# 06_RPI_USB.net
KiCad netlist of a schematic drawn in Altium Designer
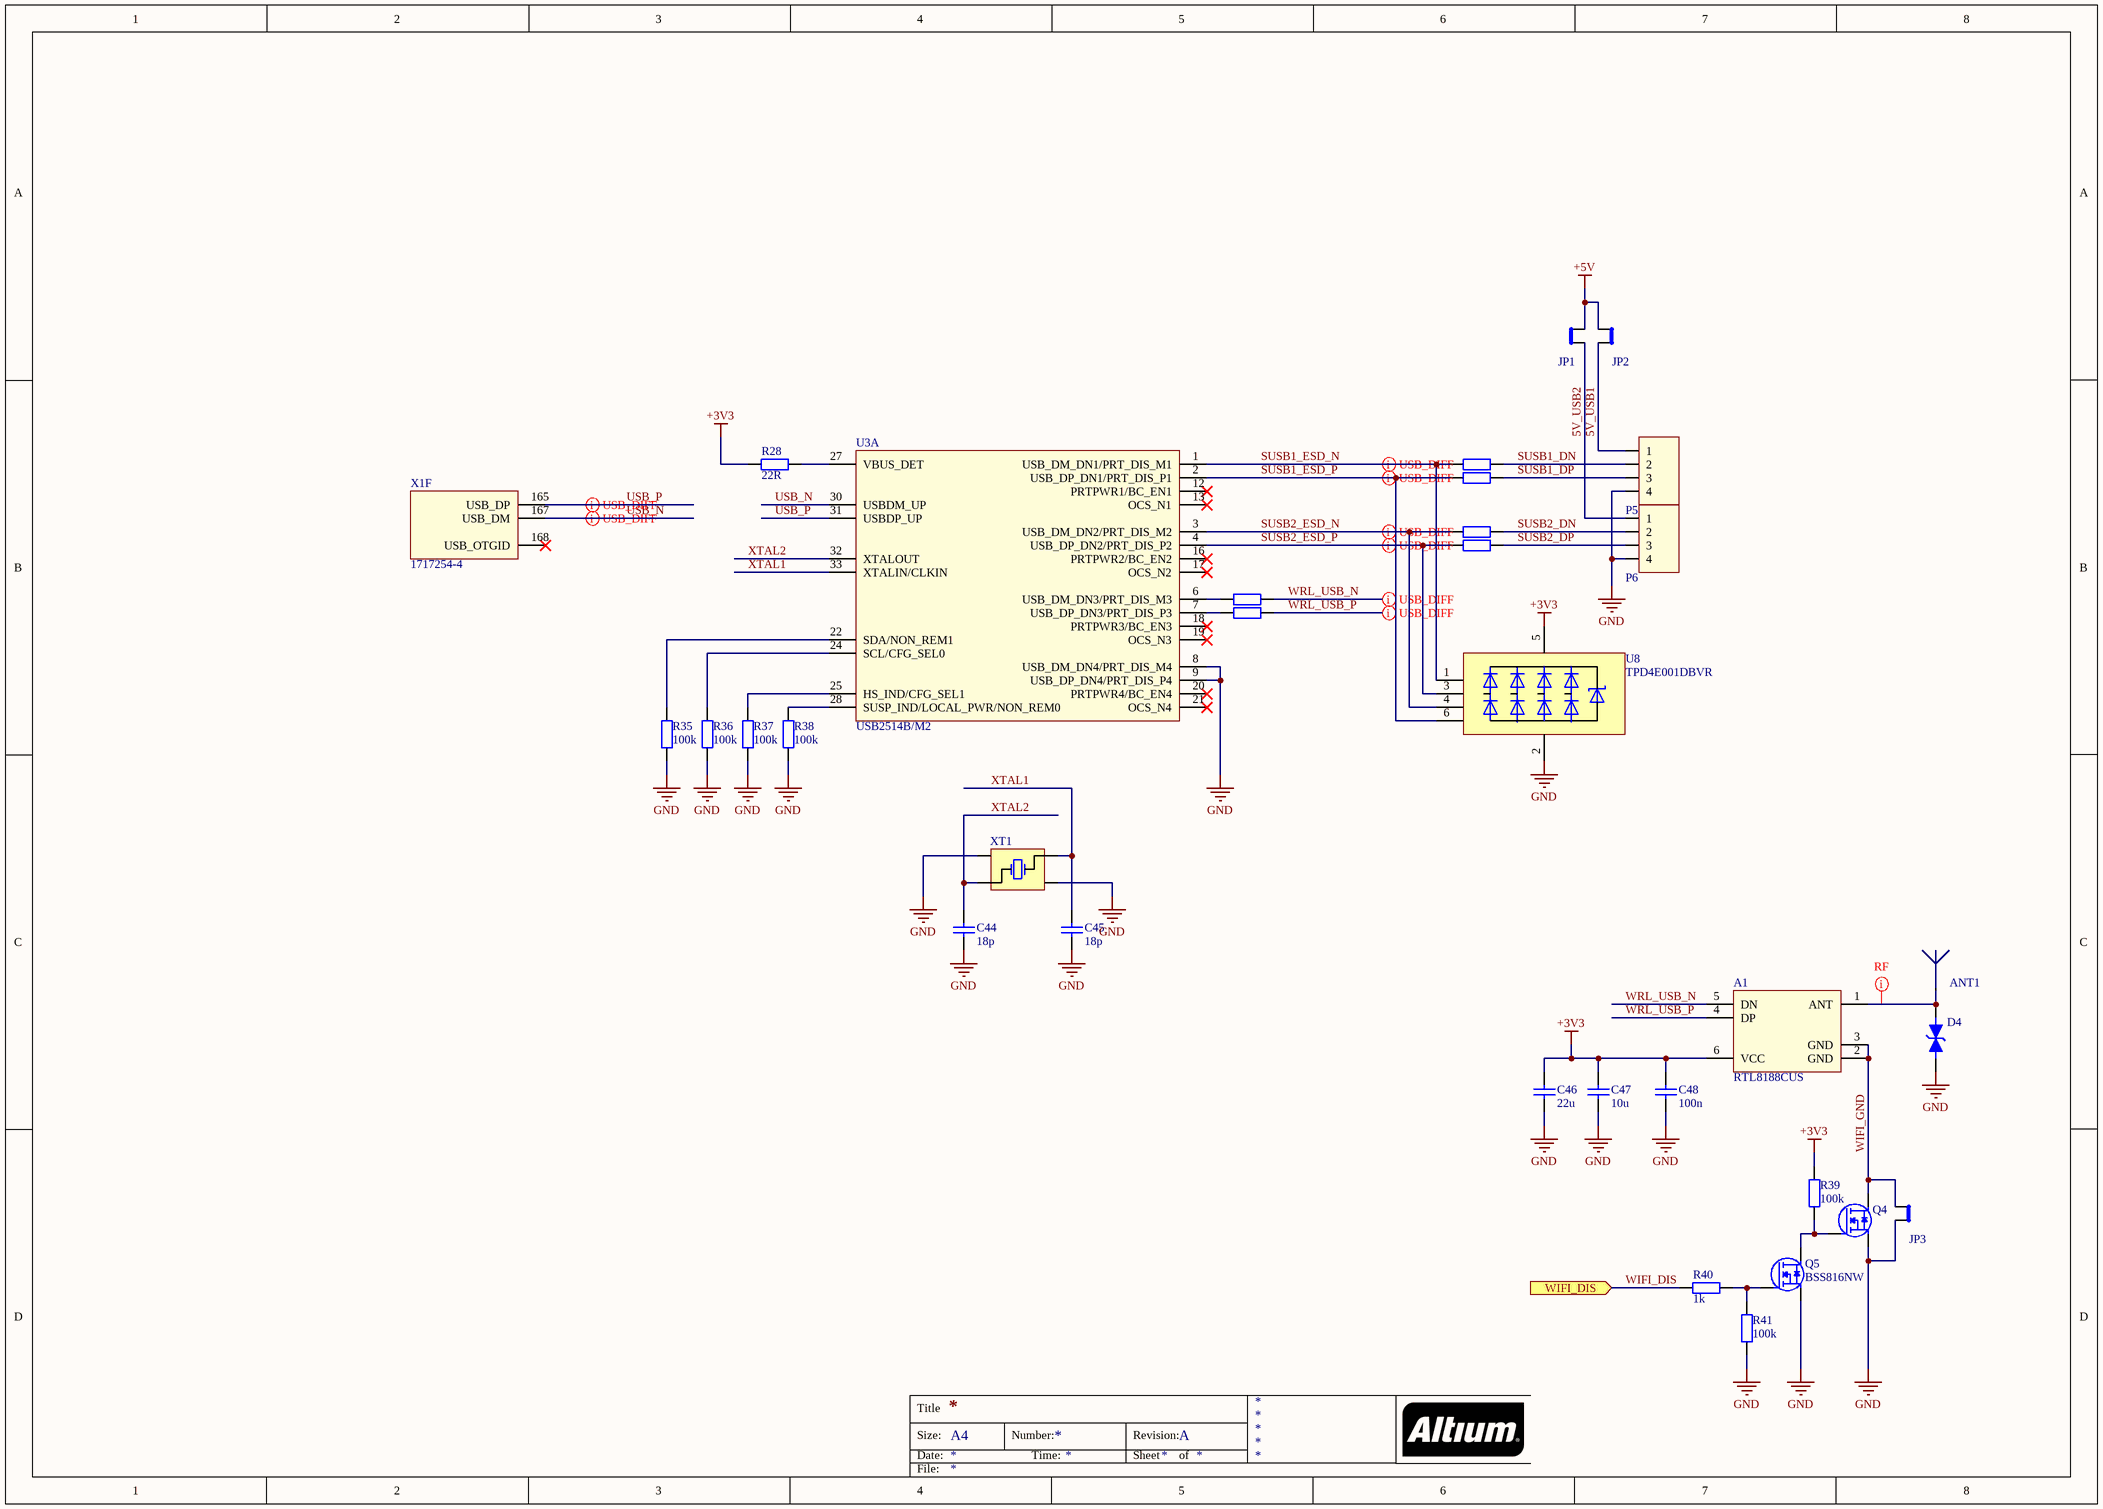
[diagram p0: 06_RPI_USB.SchDoc]

(export (version "E")
  (design (tool "Eeschema 10.0.6"))
  (components
    (comp (ref "A1")
      (value "RTL8188CUS")
      (footprint "RTL8188")
      (description "USB WiFi module")
      (fields (field (name "MANUFACTURER") "China"))
      (libsource (lib "alfasat_parts_lib") (part "RTL8188CUS"))
    )
    (comp (ref "ANT1")
      (value "ANT7020LL05R2400A")
      (footprint "ANT7020LL05")
      (description "RF ANT 2.4GHZ CHIP SOLDER SMD")
      (fields (field (name "MANUFACTURER") "Yageo"))
      (libsource (lib "alfasat_lib") (part "ANT7020LL05R2400A"))
    )
    (comp (ref "C44")
      (value "18p")
      (footprint "C0603_IPC_HD")
      (description "CAP CER 18PF 50V C0G/NP0 0603")
      (fields
        (field (name "MANUFACTURER") "Samsung Electro-Mechanics")
        (field (name "MANUFACTURER PART NUMBER") "CL10C180JB8NNNC")
      )
      (libsource (lib "alfasat_lib") (part "CL10C180JB8NNNC"))
    )
    (comp (ref "C45")
      (value "18p")
      (footprint "C0603_IPC_HD")
      (description "CAP CER 18PF 50V C0G/NP0 0603")
      (fields
        (field (name "MANUFACTURER") "Samsung Electro-Mechanics")
        (field (name "MANUFACTURER PART NUMBER") "CL10C180JB8NNNC")
      )
      (libsource (lib "alfasat_lib") (part "CL10C180JB8NNNC"))
    )
    (comp (ref "C46")
      (value "22u")
      (footprint "C0805_IPC_HD")
      (description "CAP CER 22UF 16V X5R 0805")
      (fields
        (field (name "MANUFACTURER") "Samsung Electro-Mechanics")
        (field (name "MANUFACTURER PART NUMBER") "CL21A226MOCLRNC")
      )
      (libsource (lib "alfasat_parts_lib") (part "CL21A226MOCLRNC"))
    )
    (comp (ref "C47")
      (value "10u")
      (footprint "C0805_IPC_HD")
      (description "CAP CER 10UF 16V X7R 0805")
      (fields
        (field (name "MANUFACTURER") "Samsung Electro-Mechanics")
        (field (name "MANUFACTURER PART NUMBER") "CL21B106KOQNNNG")
      )
      (libsource (lib "alfasat_lib") (part "CL21B106KOQNNNG"))
    )
    (comp (ref "C48")
      (value "100n")
      (footprint "C0603_IPC_HD")
      (description "CAP CER 0.1UF 16V X7R 0603")
      (fields
        (field (name "MANUFACTURER") "Samsung Electro-Mechanics")
        (field (name "MANUFACTURER PART NUMBER") "CL10B104KO8NNNC")
      )
      (libsource (lib "alfasat_lib") (part "CL10B104KO8NNNC"))
    )
    (comp (ref "D4")
      (value "LXES15AAA1-153")
      (footprint "C0402_IPC_MD")
      (description "TVS DIODE 4V 0402")
      (fields (field (name "MANUFACTURER") "Murata Electronics North America"))
      (libsource (lib "alfasat_lib") (part "LXES15AAA1-153"))
    )
    (comp (ref "JP1")
      (value "Jumper")
      (footprint "SolderHump1")
      (description "Jumper 2.54mm 1 pos")
      (libsource (lib "alfasat_parts_lib") (part "Jumper"))
    )
    (comp (ref "JP2")
      (value "Jumper")
      (footprint "SolderHump1")
      (description "Jumper 2.54mm 1 pos")
      (libsource (lib "alfasat_parts_lib") (part "Jumper"))
    )
    (comp (ref "JP3")
      (value "Jumper")
      (footprint "SolderHump1")
      (description "Jumper 2.54mm 1 pos")
      (libsource (lib "alfasat_parts_lib") (part "Jumper"))
    )
    (comp (ref "P5")
      (value "PicoBlade_4R")
      (footprint "PB_53261-0471_Right")
      (description "Connector Header Surface Mount 4 position 0.049\" (1.25mm)")
      (fields (field (name "MANUFACTURER") "China"))
      (libsource (lib "alfasat_lib") (part "PicoBlade_4R"))
    )
    (comp (ref "P6")
      (value "PicoBlade_4R")
      (footprint "PB_53261-0471_Right")
      (description "Connector Header Surface Mount 4 position 0.049\" (1.25mm)")
      (fields (field (name "MANUFACTURER") "China"))
      (libsource (lib "alfasat_lib") (part "PicoBlade_4R"))
    )
    (comp (ref "Q4")
      (value "DMG2302UK-7")
      (footprint "SOT23")
      (description "N-Channel Logic Level Enhancement Mode Field Effect Transistor")
      (fields (field (name "MANUFACTURER") "Diodes Incorporated"))
      (libsource (lib "alfasat_lib") (part "DMG2302"))
    )
    (comp (ref "Q5")
      (value "BSS816NW")
      (footprint "SOT323")
      (description "N-Channel Logic Level Enhancement Mode Field Effect Transistor")
      (fields (field (name "MANUFACTURER") "Infineon Technologies"))
      (libsource (lib "alfasat_parts_lib") (part "BSS816"))
    )
    (comp (ref "R28")
      (value "22R")
      (footprint "R0603_IPC_MD")
      (description "RES SMD 22 OHM 5% 1/10W 0603")
      (fields
        (field (name "MANUFACTURER") "Bourns Inc.")
        (field (name "MANUFACTURER PART NUMBER") "CR0603-JW-220ELF")
      )
      (libsource (lib "alfasat_lib") (part "CR0603-JW-220ELF"))
    )
    (comp (ref "R29")
      (value "22R")
      (footprint "R0603_IPC_MD")
      (description "RES SMD 22 OHM 5% 1/10W 0603")
      (fields
        (field (name "MANUFACTURER") "Bourns Inc.")
        (field (name "MANUFACTURER PART NUMBER") "CR0603-JW-220ELF")
      )
      (libsource (lib "alfasat_lib") (part "CR0603-JW-220ELF"))
    )
    (comp (ref "R30")
      (value "22R")
      (footprint "R0603_IPC_MD")
      (description "RES SMD 22 OHM 5% 1/10W 0603")
      (fields
        (field (name "MANUFACTURER") "Bourns Inc.")
        (field (name "MANUFACTURER PART NUMBER") "CR0603-JW-220ELF")
      )
      (libsource (lib "alfasat_lib") (part "CR0603-JW-220ELF"))
    )
    (comp (ref "R31")
      (value "22R")
      (footprint "R0603_IPC_MD")
      (description "RES SMD 22 OHM 5% 1/10W 0603")
      (fields
        (field (name "MANUFACTURER") "Bourns Inc.")
        (field (name "MANUFACTURER PART NUMBER") "CR0603-JW-220ELF")
      )
      (libsource (lib "alfasat_lib") (part "CR0603-JW-220ELF"))
    )
    (comp (ref "R32")
      (value "22R")
      (footprint "R0603_IPC_MD")
      (description "RES SMD 22 OHM 5% 1/10W 0603")
      (fields
        (field (name "MANUFACTURER") "Bourns Inc.")
        (field (name "MANUFACTURER PART NUMBER") "CR0603-JW-220ELF")
      )
      (libsource (lib "alfasat_lib") (part "CR0603-JW-220ELF"))
    )
    (comp (ref "R33")
      (value "22R")
      (footprint "R0603_IPC_MD")
      (description "RES SMD 22 OHM 5% 1/10W 0603")
      (fields
        (field (name "MANUFACTURER") "Bourns Inc.")
        (field (name "MANUFACTURER PART NUMBER") "CR0603-JW-220ELF")
      )
      (libsource (lib "alfasat_lib") (part "CR0603-JW-220ELF"))
    )
    (comp (ref "R34")
      (value "22R")
      (footprint "R0603_IPC_MD")
      (description "RES SMD 22 OHM 5% 1/10W 0603")
      (fields
        (field (name "MANUFACTURER") "Bourns Inc.")
        (field (name "MANUFACTURER PART NUMBER") "CR0603-JW-220ELF")
      )
      (libsource (lib "alfasat_lib") (part "CR0603-JW-220ELF"))
    )
    (comp (ref "R35")
      (value "100k")
      (footprint "R0603_IPC_MD")
      (description "RES 100K OHM 1% 1/10W 0603")
      (fields
        (field (name "MANUFACTURER") "Bourns Inc.")
        (field (name "MANUFACTURER PART NUMBER") "RMCF0603FT100K")
      )
      (libsource (lib "alfasat_lib") (part "RMCF0603FT100K"))
    )
    (comp (ref "R36")
      (value "100k")
      (footprint "R0603_IPC_MD")
      (description "RES 100K OHM 1% 1/10W 0603")
      (fields
        (field (name "MANUFACTURER") "Bourns Inc.")
        (field (name "MANUFACTURER PART NUMBER") "RMCF0603FT100K")
      )
      (libsource (lib "alfasat_lib") (part "RMCF0603FT100K"))
    )
    (comp (ref "R37")
      (value "100k")
      (footprint "R0603_IPC_MD")
      (description "RES 100K OHM 1% 1/10W 0603")
      (fields
        (field (name "MANUFACTURER") "Bourns Inc.")
        (field (name "MANUFACTURER PART NUMBER") "RMCF0603FT100K")
      )
      (libsource (lib "alfasat_lib") (part "RMCF0603FT100K"))
    )
    (comp (ref "R38")
      (value "100k")
      (footprint "R0603_IPC_MD")
      (description "RES 100K OHM 1% 1/10W 0603")
      (fields
        (field (name "MANUFACTURER") "Bourns Inc.")
        (field (name "MANUFACTURER PART NUMBER") "RMCF0603FT100K")
      )
      (libsource (lib "alfasat_lib") (part "RMCF0603FT100K"))
    )
    (comp (ref "R39")
      (value "100k")
      (footprint "R0603_IPC_MD")
      (description "RES 100K OHM 1% 1/10W 0603")
      (fields
        (field (name "MANUFACTURER") "Bourns Inc.")
        (field (name "MANUFACTURER PART NUMBER") "RMCF0603FT100K")
      )
      (libsource (lib "alfasat_lib") (part "RMCF0603FT100K"))
    )
    (comp (ref "R40")
      (value "1k")
      (footprint "R0603_IPC_MD")
      (description "RES SMD 1K OHM 5% 1/10W 0603")
      (fields
        (field (name "MANUFACTURER") "Bourns Inc.")
        (field (name "MANUFACTURER PART NUMBER") "CR0603-JW-102ELF")
      )
      (libsource (lib "alfasat_lib") (part "CR0603-JW-102ELF"))
    )
    (comp (ref "R41")
      (value "100k")
      (footprint "R0603_IPC_MD")
      (description "RES 100K OHM 1% 1/10W 0603")
      (fields
        (field (name "MANUFACTURER") "Bourns Inc.")
        (field (name "MANUFACTURER PART NUMBER") "RMCF0603FT100K")
      )
      (libsource (lib "alfasat_lib") (part "RMCF0603FT100K"))
    )
    (comp (ref "U3")
      (value "USB2514B/M2")
      (footprint "QFN36")
      (description "IC HUB CTLR 4PORT USB 2.0 HS 36S")
      (fields (field (name "MANUFACTURER") "Microchip Technology"))
      (libsource (lib "alfasat_lib") (part "USB2514B/M2"))
    )
    (comp (ref "U8")
      (value "TPD4E001DBVR")
      (footprint "SOT23-6")
      (description "4x TVS DIODE 5.5V SOT23-6")
      (fields (field (name "MANUFACTURER") "TI"))
      (libsource (lib "alfasat_lib") (part "TPD4E001DBVR"))
    )
    (comp (ref "X1")
      (value "1717254-4")
      (footprint "1717254-1")
      (description "CONN SKT SODIMM 200POS R/A SMD")
      (fields (field (name "MANUFACTURER") "TE Connectivity AMP Connectors"))
      (libsource (lib "alfasat_lib") (part "Raspberry CM Connector"))
    )
    (comp (ref "XT1")
      (value "TSX-3225-24.0000MF15X-AC6")
      (footprint "3.2x2.5_4pad_smd")
      (description "CRYSTAL 24.00 MHZ 9.0PF SMD")
      (fields (field (name "MANUFACTURER") "EPSON"))
      (libsource (lib "alfasat_lib") (part "TSX-3225-24.0000MF15X-AC61"))
    )
  )
  (nets
    (net (code "1") (name "+3V3") (class "Default")
      (node (ref "A1") (pin "6") (pinfunction "VCC_6") (pintype "passive"))
      (node (ref "C46") (pin "1") (pinfunction "1_1") (pintype "passive"))
      (node (ref "C47") (pin "2") (pinfunction "2_2") (pintype "passive"))
      (node (ref "C48") (pin "2") (pinfunction "2_2") (pintype "passive"))
      (node (ref "R28") (pin "1") (pinfunction "1_1") (pintype "passive"))
      (node (ref "R39") (pin "2") (pinfunction "2_2") (pintype "passive"))
      (node (ref "U8") (pin "5") (pinfunction "VCC_5") (pintype "power_in"))
    )
    (net (code "2") (name "+5V") (class "Default")
      (node (ref "JP1") (pin "2") (pinfunction "2_2") (pintype "passive"))
      (node (ref "JP2") (pin "2") (pinfunction "2_2") (pintype "passive"))
    )
    (net (code "3") (name "/5V_USB1") (class "Default")
      (node (ref "JP2") (pin "1") (pinfunction "1_1") (pintype "passive"))
      (node (ref "P5") (pin "1") (pinfunction "1_1") (pintype "passive"))
    )
    (net (code "4") (name "/5V_USB2") (class "Default")
      (node (ref "JP1") (pin "1") (pinfunction "1_1") (pintype "passive"))
      (node (ref "P6") (pin "1") (pinfunction "1_1") (pintype "passive"))
    )
    (net (code "5") (name "/SUSB1_DN") (class "Default")
      (node (ref "P5") (pin "2") (pinfunction "2_2") (pintype "passive"))
      (node (ref "R29") (pin "2") (pinfunction "2_2") (pintype "passive"))
    )
    (net (code "6") (name "/SUSB1_DP") (class "Default")
      (node (ref "P5") (pin "3") (pinfunction "3_3") (pintype "passive"))
      (node (ref "R30") (pin "2") (pinfunction "2_2") (pintype "passive"))
    )
    (net (code "7") (name "/SUSB1_ESD_N") (class "Default")
      (node (ref "R29") (pin "1") (pinfunction "1_1") (pintype "passive"))
      (node (ref "U3") (pin "1") (pinfunction "USB_DM_DN1/PRT_DIS_M1_1") (pintype "passive"))
      (node (ref "U8") (pin "1") (pinfunction "IO1_1") (pintype "passive"))
    )
    (net (code "8") (name "/SUSB1_ESD_P") (class "Default")
      (node (ref "R30") (pin "1") (pinfunction "1_1") (pintype "passive"))
      (node (ref "U3") (pin "2") (pinfunction "USB_DP_DN1/PRT_DIS_P1_2") (pintype "passive"))
      (node (ref "U8") (pin "6") (pinfunction "IO4_6") (pintype "passive"))
    )
    (net (code "9") (name "/SUSB2_DN") (class "Default")
      (node (ref "P6") (pin "2") (pinfunction "2_2") (pintype "passive"))
      (node (ref "R31") (pin "2") (pinfunction "2_2") (pintype "passive"))
    )
    (net (code "10") (name "/SUSB2_DP") (class "Default")
      (node (ref "P6") (pin "3") (pinfunction "3_3") (pintype "passive"))
      (node (ref "R32") (pin "2") (pinfunction "2_2") (pintype "passive"))
    )
    (net (code "11") (name "/SUSB2_ESD_N") (class "Default")
      (node (ref "R31") (pin "1") (pinfunction "1_1") (pintype "passive"))
      (node (ref "U3") (pin "3") (pinfunction "USB_DM_DN2/PRT_DIS_M2_3") (pintype "passive"))
      (node (ref "U8") (pin "4") (pinfunction "IO3_4") (pintype "passive"))
    )
    (net (code "12") (name "/SUSB2_ESD_P") (class "Default")
      (node (ref "R32") (pin "1") (pinfunction "1_1") (pintype "passive"))
      (node (ref "U3") (pin "4") (pinfunction "USB_DP_DN2/PRT_DIS_P2_4") (pintype "passive"))
      (node (ref "U8") (pin "3") (pinfunction "IO2_3") (pintype "passive"))
    )
    (net (code "13") (name "/USB_N") (class "Default")
      (node (ref "U3") (pin "30") (pinfunction "USBDM_UP_30") (pintype "passive"))
      (node (ref "X1") (pin "167") (pinfunction "USB_DM_167") (pintype "passive"))
    )
    (net (code "14") (name "/USB_P") (class "Default")
      (node (ref "U3") (pin "31") (pinfunction "USBDP_UP_31") (pintype "passive"))
      (node (ref "X1") (pin "165") (pinfunction "USB_DP_165") (pintype "passive"))
    )
    (net (code "15") (name "/WIFI_DIS") (class "Default")
      (node (ref "R40") (pin "1") (pinfunction "1_1") (pintype "passive"))
    )
    (net (code "16") (name "/WIFI_GND") (class "Default")
      (node (ref "A1") (pin "2") (pinfunction "GND_2") (pintype "passive"))
      (node (ref "A1") (pin "3") (pinfunction "GND_3") (pintype "passive"))
      (node (ref "JP3") (pin "2") (pinfunction "2_2") (pintype "passive"))
      (node (ref "Q4") (pin "3") (pinfunction "D_3") (pintype "passive"))
    )
    (net (code "17") (name "/WRL_USB_N") (class "Default")
      (node (ref "A1") (pin "5") (pinfunction "DN_5") (pintype "passive"))
      (node (ref "R33") (pin "2") (pinfunction "2_2") (pintype "passive"))
    )
    (net (code "18") (name "/WRL_USB_P") (class "Default")
      (node (ref "A1") (pin "4") (pinfunction "DP_4") (pintype "passive"))
      (node (ref "R34") (pin "2") (pinfunction "2_2") (pintype "passive"))
    )
    (net (code "19") (name "/XTAL1") (class "Default")
      (node (ref "C45") (pin "2") (pinfunction "2_2") (pintype "passive"))
      (node (ref "U3") (pin "33") (pinfunction "XTALIN/CLKIN_33") (pintype "passive"))
      (node (ref "XT1") (pin "1") (pinfunction "OSC1_1") (pintype "passive"))
    )
    (net (code "20") (name "/XTAL2") (class "Default")
      (node (ref "C44") (pin "2") (pinfunction "2_2") (pintype "passive"))
      (node (ref "U3") (pin "32") (pinfunction "XTALOUT_32") (pintype "passive"))
      (node (ref "XT1") (pin "3") (pinfunction "OSC2_3") (pintype "passive"))
    )
    (net (code "21") (name "GND") (class "Default")
      (node (ref "C44") (pin "1") (pinfunction "1_1") (pintype "passive"))
      (node (ref "C45") (pin "1") (pinfunction "1_1") (pintype "passive"))
      (node (ref "C46") (pin "2") (pinfunction "2_2") (pintype "passive"))
      (node (ref "C47") (pin "1") (pinfunction "1_1") (pintype "passive"))
      (node (ref "C48") (pin "1") (pinfunction "1_1") (pintype "passive"))
      (node (ref "D4") (pin "1") (pinfunction "1_1") (pintype "passive"))
      (node (ref "JP3") (pin "1") (pinfunction "1_1") (pintype "passive"))
      (node (ref "P5") (pin "4") (pinfunction "4_4") (pintype "passive"))
      (node (ref "P6") (pin "4") (pinfunction "4_4") (pintype "passive"))
      (node (ref "Q4") (pin "2") (pinfunction "S_2") (pintype "passive"))
      (node (ref "Q5") (pin "2") (pinfunction "S_2") (pintype "passive"))
      (node (ref "R35") (pin "1") (pinfunction "1_1") (pintype "passive"))
      (node (ref "R36") (pin "1") (pinfunction "1_1") (pintype "passive"))
      (node (ref "R37") (pin "1") (pinfunction "1_1") (pintype "passive"))
      (node (ref "R38") (pin "1") (pinfunction "1_1") (pintype "passive"))
      (node (ref "R41") (pin "1") (pinfunction "1_1") (pintype "passive"))
      (node (ref "U3") (pin "8") (pinfunction "USB_DM_DN4/PRT_DIS_M4_8") (pintype "passive"))
      (node (ref "U3") (pin "9") (pinfunction "USB_DP_DN4/PRT_DIS_P4_9") (pintype "passive"))
      (node (ref "U8") (pin "2") (pinfunction "GND_2") (pintype "power_in"))
      (node (ref "XT1") (pin "2") (pinfunction "NC_2") (pintype "passive"))
      (node (ref "XT1") (pin "4") (pinfunction "NC_4") (pintype "passive"))
    )
    (net (code "22") (name "Net-(A1-ANT)") (class "Default")
      (node (ref "A1") (pin "1") (pinfunction "ANT_1") (pintype "passive"))
      (node (ref "ANT1") (pin "1") (pinfunction "1_1") (pintype "passive"))
      (node (ref "D4") (pin "2") (pinfunction "2_2") (pintype "passive"))
    )
    (net (code "23") (name "Net-(Q4-G)") (class "Default")
      (node (ref "Q4") (pin "1") (pinfunction "G_1") (pintype "passive"))
      (node (ref "Q5") (pin "3") (pinfunction "D_3") (pintype "passive"))
      (node (ref "R39") (pin "1") (pinfunction "1_1") (pintype "passive"))
    )
    (net (code "24") (name "Net-(Q5-G)") (class "Default")
      (node (ref "Q5") (pin "1") (pinfunction "G_1") (pintype "passive"))
      (node (ref "R40") (pin "2") (pinfunction "2_2") (pintype "passive"))
      (node (ref "R41") (pin "2") (pinfunction "2_2") (pintype "passive"))
    )
    (net (code "25") (name "Net-(U3A-HS_IND{slash}CFG_SEL1)") (class "Default")
      (node (ref "R37") (pin "2") (pinfunction "2_2") (pintype "passive"))
      (node (ref "U3") (pin "25") (pinfunction "HS_IND/CFG_SEL1_25") (pintype "passive"))
    )
    (net (code "26") (name "Net-(U3A-SCL{slash}CFG_SEL0)") (class "Default")
      (node (ref "R36") (pin "2") (pinfunction "2_2") (pintype "passive"))
      (node (ref "U3") (pin "24") (pinfunction "SCL/CFG_SEL0_24") (pintype "passive"))
    )
    (net (code "27") (name "Net-(U3A-SDA{slash}NON_REM1)") (class "Default")
      (node (ref "R35") (pin "2") (pinfunction "2_2") (pintype "passive"))
      (node (ref "U3") (pin "22") (pinfunction "SDA/NON_REM1_22") (pintype "passive"))
    )
    (net (code "28") (name "Net-(U3A-SUSP_IND{slash}LOCAL_PWR{slash}NON_REM0)") (class "Default")
      (node (ref "R38") (pin "2") (pinfunction "2_2") (pintype "passive"))
      (node (ref "U3") (pin "28") (pinfunction "SUSP_IND/LOCAL_PWR/NON_REM0_28") (pintype "passive"))
    )
    (net (code "29") (name "Net-(U3A-USB_DM_DN3{slash}PRT_DIS_M3)") (class "Default")
      (node (ref "R33") (pin "1") (pinfunction "1_1") (pintype "passive"))
      (node (ref "U3") (pin "6") (pinfunction "USB_DM_DN3/PRT_DIS_M3_6") (pintype "passive"))
    )
    (net (code "30") (name "Net-(U3A-USB_DP_DN3{slash}PRT_DIS_P3)") (class "Default")
      (node (ref "R34") (pin "1") (pinfunction "1_1") (pintype "passive"))
      (node (ref "U3") (pin "7") (pinfunction "USB_DP_DN3/PRT_DIS_P3_7") (pintype "passive"))
    )
    (net (code "31") (name "Net-(U3A-VBUS_DET)") (class "Default")
      (node (ref "R28") (pin "2") (pinfunction "2_2") (pintype "passive"))
      (node (ref "U3") (pin "27") (pinfunction "VBUS_DET_27") (pintype "passive"))
    )
    (net (code "32") (name "unconnected-(U3A-OCS_N1-Pad13)") (class "Default")
      (node (ref "U3") (pin "13") (pinfunction "OCS_N1_13") (pintype "passive+no_connect"))
    )
    (net (code "33") (name "unconnected-(U3A-OCS_N2-Pad17)") (class "Default")
      (node (ref "U3") (pin "17") (pinfunction "OCS_N2_17") (pintype "passive+no_connect"))
    )
    (net (code "34") (name "unconnected-(U3A-OCS_N3-Pad19)") (class "Default")
      (node (ref "U3") (pin "19") (pinfunction "OCS_N3_19") (pintype "passive+no_connect"))
    )
    (net (code "35") (name "unconnected-(U3A-OCS_N4-Pad21)") (class "Default")
      (node (ref "U3") (pin "21") (pinfunction "OCS_N4_21") (pintype "passive+no_connect"))
    )
    (net (code "36") (name "unconnected-(U3A-PRTPWR1{slash}BC_EN1-Pad12)") (class "Default")
      (node (ref "U3") (pin "12") (pinfunction "PRTPWR1/BC_EN1_12") (pintype "passive+no_connect"))
    )
    (net (code "37") (name "unconnected-(U3A-PRTPWR2{slash}BC_EN2-Pad16)") (class "Default")
      (node (ref "U3") (pin "16") (pinfunction "PRTPWR2/BC_EN2_16") (pintype "passive+no_connect"))
    )
    (net (code "38") (name "unconnected-(U3A-PRTPWR3{slash}BC_EN3-Pad18)") (class "Default")
      (node (ref "U3") (pin "18") (pinfunction "PRTPWR3/BC_EN3_18") (pintype "passive+no_connect"))
    )
    (net (code "39") (name "unconnected-(U3A-PRTPWR4{slash}BC_EN4-Pad20)") (class "Default")
      (node (ref "U3") (pin "20") (pinfunction "PRTPWR4/BC_EN4_20") (pintype "passive+no_connect"))
    )
    (net (code "40") (name "unconnected-(X1F-USB_OTGID-Pad168)") (class "Default")
      (node (ref "X1") (pin "168") (pinfunction "USB_OTGID_168") (pintype "passive+no_connect"))
    )
  )
)
